# BeatleBoy.net
KiCad netlist of a schematic drawn in EAGLE
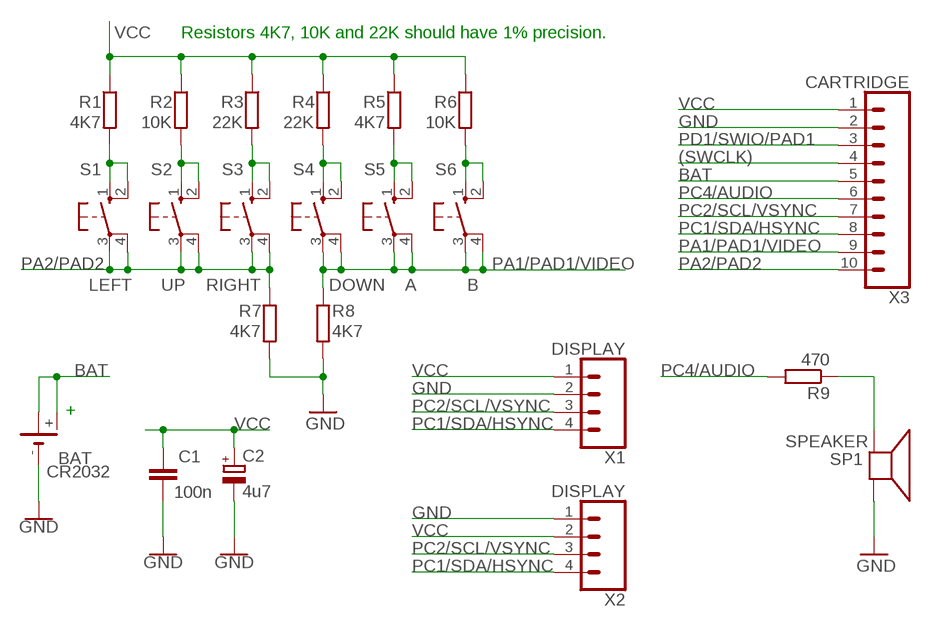
[diagram p0: schematic, sheet 1]

(export (version "E")
  (design (tool "Eeschema 10.0.6"))
  (components
    (comp (ref "BAT")
      (value "CR2032")
      (footprint "eagle-import:CR2032H")
      (libsource (lib "eagle-import") (part "CR2032H"))
    )
    (comp (ref "C1")
      (value "100n")
      (footprint "eagle-import:C025-024X044")
      (libsource (lib "eagle-import") (part "C-EU025-024X044"))
    )
    (comp (ref "C2")
      (value "4u7")
      (footprint "eagle-import:E2-4")
      (libsource (lib "eagle-import") (part "CPOL-EUE2-4"))
    )
    (comp (ref "R1")
      (value "4K7")
      (footprint "eagle-import:0204V")
      (libsource (lib "eagle-import") (part "R-EU_0204/2V"))
    )
    (comp (ref "R2")
      (value "10K")
      (footprint "eagle-import:0204V")
      (libsource (lib "eagle-import") (part "R-EU_0204/2V"))
    )
    (comp (ref "R3")
      (value "22K")
      (footprint "eagle-import:0204V")
      (libsource (lib "eagle-import") (part "R-EU_0204/2V"))
    )
    (comp (ref "R4")
      (value "22K")
      (footprint "eagle-import:0204V")
      (libsource (lib "eagle-import") (part "R-EU_0204/2V"))
    )
    (comp (ref "R5")
      (value "4K7")
      (footprint "eagle-import:0204V")
      (libsource (lib "eagle-import") (part "R-EU_0204/2V"))
    )
    (comp (ref "R6")
      (value "10K")
      (footprint "eagle-import:0204V")
      (libsource (lib "eagle-import") (part "R-EU_0204/2V"))
    )
    (comp (ref "R7")
      (value "4K7")
      (footprint "eagle-import:0204V")
      (libsource (lib "eagle-import") (part "R-EU_0204/2V"))
    )
    (comp (ref "R8")
      (value "4K7")
      (footprint "eagle-import:0204V")
      (libsource (lib "eagle-import") (part "R-EU_0204/2V"))
    )
    (comp (ref "R9")
      (value "470")
      (footprint "eagle-import:0204V")
      (libsource (lib "eagle-import") (part "R-EU_0204/2V"))
    )
    (comp (ref "S1")
      (value "LEFT")
      (footprint "eagle-import:B3F-10XXB")
      (libsource (lib "eagle-import") (part "10-XXB3F-10XXB"))
    )
    (comp (ref "S2")
      (value "UP")
      (footprint "eagle-import:B3F-10XXB")
      (libsource (lib "eagle-import") (part "10-XXB3F-10XXB"))
    )
    (comp (ref "S3")
      (value "RIGHT")
      (footprint "eagle-import:B3F-10XXB")
      (libsource (lib "eagle-import") (part "10-XXB3F-10XXB"))
    )
    (comp (ref "S4")
      (value "DOWN")
      (footprint "eagle-import:B3F-10XXB")
      (libsource (lib "eagle-import") (part "10-XXB3F-10XXB"))
    )
    (comp (ref "S5")
      (value "A")
      (footprint "eagle-import:B3F-10XXB")
      (libsource (lib "eagle-import") (part "10-XXB3F-10XXB"))
    )
    (comp (ref "S6")
      (value "B")
      (footprint "eagle-import:B3F-10XXB")
      (libsource (lib "eagle-import") (part "10-XXB3F-10XXB"))
    )
    (comp (ref "SP1")
      (value "SPEAKER")
      (footprint "eagle-import:AL60P")
      (libsource (lib "eagle-import") (part "SPEAKER/AL60P"))
    )
    (comp (ref "X1")
      (value "DISPLAY")
      (footprint "eagle-import:1X04")
      (libsource (lib "eagle-import") (part "CONN_04"))
    )
    (comp (ref "X2")
      (value "DISPLAY")
      (footprint "eagle-import:1X04")
      (libsource (lib "eagle-import") (part "CONN_04"))
    )
    (comp (ref "X3")
      (value "CARTRIDGE")
      (footprint "eagle-import:1X10_LONGPADS")
      (libsource (lib "eagle-import") (part "CONN_10"))
    )
  )
  (nets
    (net (code "1") (name "/(SWCLK)") (class "Default")
      (node (ref "X3") (pin "4") (pinfunction "4_4") (pintype "passive"))
    )
    (net (code "2") (name "/BAT") (class "Default")
      (node (ref "BAT") (pin "+") (pinfunction "+_+") (pintype "passive"))
      (node (ref "BAT") (pin "+@1") (pinfunction "+_+@1") (pintype "passive"))
      (node (ref "X3") (pin "5") (pinfunction "5_5") (pintype "passive"))
    )
    (net (code "3") (name "/PA1{slash}PAD1{slash}VIDEO") (class "Default")
      (node (ref "R8") (pin "1") (pinfunction "1_1") (pintype "passive"))
      (node (ref "S4") (pin "3") (pinfunction "P_3") (pintype "passive"))
      (node (ref "S4") (pin "4") (pinfunction "P1_4") (pintype "passive"))
      (node (ref "S5") (pin "3") (pinfunction "P_3") (pintype "passive"))
      (node (ref "S5") (pin "4") (pinfunction "P1_4") (pintype "passive"))
      (node (ref "S6") (pin "3") (pinfunction "P_3") (pintype "passive"))
      (node (ref "S6") (pin "4") (pinfunction "P1_4") (pintype "passive"))
      (node (ref "X3") (pin "9") (pinfunction "9_9") (pintype "passive"))
    )
    (net (code "4") (name "/PA2{slash}PAD2") (class "Default")
      (node (ref "R7") (pin "1") (pinfunction "1_1") (pintype "passive"))
      (node (ref "S1") (pin "3") (pinfunction "P_3") (pintype "passive"))
      (node (ref "S1") (pin "4") (pinfunction "P1_4") (pintype "passive"))
      (node (ref "S2") (pin "3") (pinfunction "P_3") (pintype "passive"))
      (node (ref "S2") (pin "4") (pinfunction "P1_4") (pintype "passive"))
      (node (ref "S3") (pin "3") (pinfunction "P_3") (pintype "passive"))
      (node (ref "S3") (pin "4") (pinfunction "P1_4") (pintype "passive"))
      (node (ref "X3") (pin "10") (pinfunction "10_10") (pintype "passive"))
    )
    (net (code "5") (name "/PC1{slash}SDA{slash}HSYNC") (class "Default")
      (node (ref "X1") (pin "4") (pinfunction "4_4") (pintype "passive"))
      (node (ref "X2") (pin "4") (pinfunction "4_4") (pintype "passive"))
      (node (ref "X3") (pin "8") (pinfunction "8_8") (pintype "passive"))
    )
    (net (code "6") (name "/PC2{slash}SCL{slash}VSYNC") (class "Default")
      (node (ref "X1") (pin "3") (pinfunction "3_3") (pintype "passive"))
      (node (ref "X2") (pin "3") (pinfunction "3_3") (pintype "passive"))
      (node (ref "X3") (pin "7") (pinfunction "7_7") (pintype "passive"))
    )
    (net (code "7") (name "/PC4{slash}AUDIO") (class "Default")
      (node (ref "R9") (pin "2") (pinfunction "2_2") (pintype "passive"))
      (node (ref "X3") (pin "6") (pinfunction "6_6") (pintype "passive"))
    )
    (net (code "8") (name "/PD1{slash}SWIO{slash}PAD1") (class "Default")
      (node (ref "X3") (pin "3") (pinfunction "3_3") (pintype "passive"))
    )
    (net (code "9") (name "/VCC") (class "Default")
      (node (ref "C1") (pin "1") (pinfunction "1_1") (pintype "passive"))
      (node (ref "C2") (pin "+") (pinfunction "+_+") (pintype "passive"))
      (node (ref "R1") (pin "1") (pinfunction "1_1") (pintype "passive"))
      (node (ref "R2") (pin "1") (pinfunction "1_1") (pintype "passive"))
      (node (ref "R3") (pin "1") (pinfunction "1_1") (pintype "passive"))
      (node (ref "R4") (pin "1") (pinfunction "1_1") (pintype "passive"))
      (node (ref "R5") (pin "1") (pinfunction "1_1") (pintype "passive"))
      (node (ref "R6") (pin "1") (pinfunction "1_1") (pintype "passive"))
      (node (ref "X1") (pin "1") (pinfunction "1_1") (pintype "passive"))
      (node (ref "X2") (pin "2") (pinfunction "2_2") (pintype "passive"))
      (node (ref "X3") (pin "1") (pinfunction "1_1") (pintype "passive"))
    )
    (net (code "10") (name "GND") (class "Default")
      (node (ref "BAT") (pin "-") (pinfunction "-_-") (pintype "passive"))
      (node (ref "C1") (pin "2") (pinfunction "2_2") (pintype "passive"))
      (node (ref "C2") (pin "-") (pinfunction "-_-") (pintype "passive"))
      (node (ref "R7") (pin "2") (pinfunction "2_2") (pintype "passive"))
      (node (ref "R8") (pin "2") (pinfunction "2_2") (pintype "passive"))
      (node (ref "SP1") (pin "2") (pinfunction "-_2") (pintype "passive"))
      (node (ref "X1") (pin "2") (pinfunction "2_2") (pintype "passive"))
      (node (ref "X2") (pin "1") (pinfunction "1_1") (pintype "passive"))
      (node (ref "X3") (pin "2") (pinfunction "2_2") (pintype "passive"))
    )
    (net (code "11") (name "Net-(S1-S)") (class "Default")
      (node (ref "R1") (pin "2") (pinfunction "2_2") (pintype "passive"))
      (node (ref "S1") (pin "1") (pinfunction "S_1") (pintype "passive"))
      (node (ref "S1") (pin "2") (pinfunction "S1_2") (pintype "passive"))
    )
    (net (code "12") (name "Net-(S2-S)") (class "Default")
      (node (ref "R2") (pin "2") (pinfunction "2_2") (pintype "passive"))
      (node (ref "S2") (pin "1") (pinfunction "S_1") (pintype "passive"))
      (node (ref "S2") (pin "2") (pinfunction "S1_2") (pintype "passive"))
    )
    (net (code "13") (name "Net-(S3-S)") (class "Default")
      (node (ref "R3") (pin "2") (pinfunction "2_2") (pintype "passive"))
      (node (ref "S3") (pin "1") (pinfunction "S_1") (pintype "passive"))
      (node (ref "S3") (pin "2") (pinfunction "S1_2") (pintype "passive"))
    )
    (net (code "14") (name "Net-(S4-S)") (class "Default")
      (node (ref "R4") (pin "2") (pinfunction "2_2") (pintype "passive"))
      (node (ref "S4") (pin "1") (pinfunction "S_1") (pintype "passive"))
      (node (ref "S4") (pin "2") (pinfunction "S1_2") (pintype "passive"))
    )
    (net (code "15") (name "Net-(S5-S)") (class "Default")
      (node (ref "R5") (pin "2") (pinfunction "2_2") (pintype "passive"))
      (node (ref "S5") (pin "1") (pinfunction "S_1") (pintype "passive"))
      (node (ref "S5") (pin "2") (pinfunction "S1_2") (pintype "passive"))
    )
    (net (code "16") (name "Net-(S6-S)") (class "Default")
      (node (ref "R6") (pin "2") (pinfunction "2_2") (pintype "passive"))
      (node (ref "S6") (pin "1") (pinfunction "S_1") (pintype "passive"))
      (node (ref "S6") (pin "2") (pinfunction "S1_2") (pintype "passive"))
    )
    (net (code "17") (name "Net-(SP1-+)") (class "Default")
      (node (ref "R9") (pin "1") (pinfunction "1_1") (pintype "passive"))
      (node (ref "SP1") (pin "1") (pinfunction "+_1") (pintype "passive"))
    )
  )
)
